# TPaletteWindow.net
KiCad netlist of a schematic drawn in Altium Designer
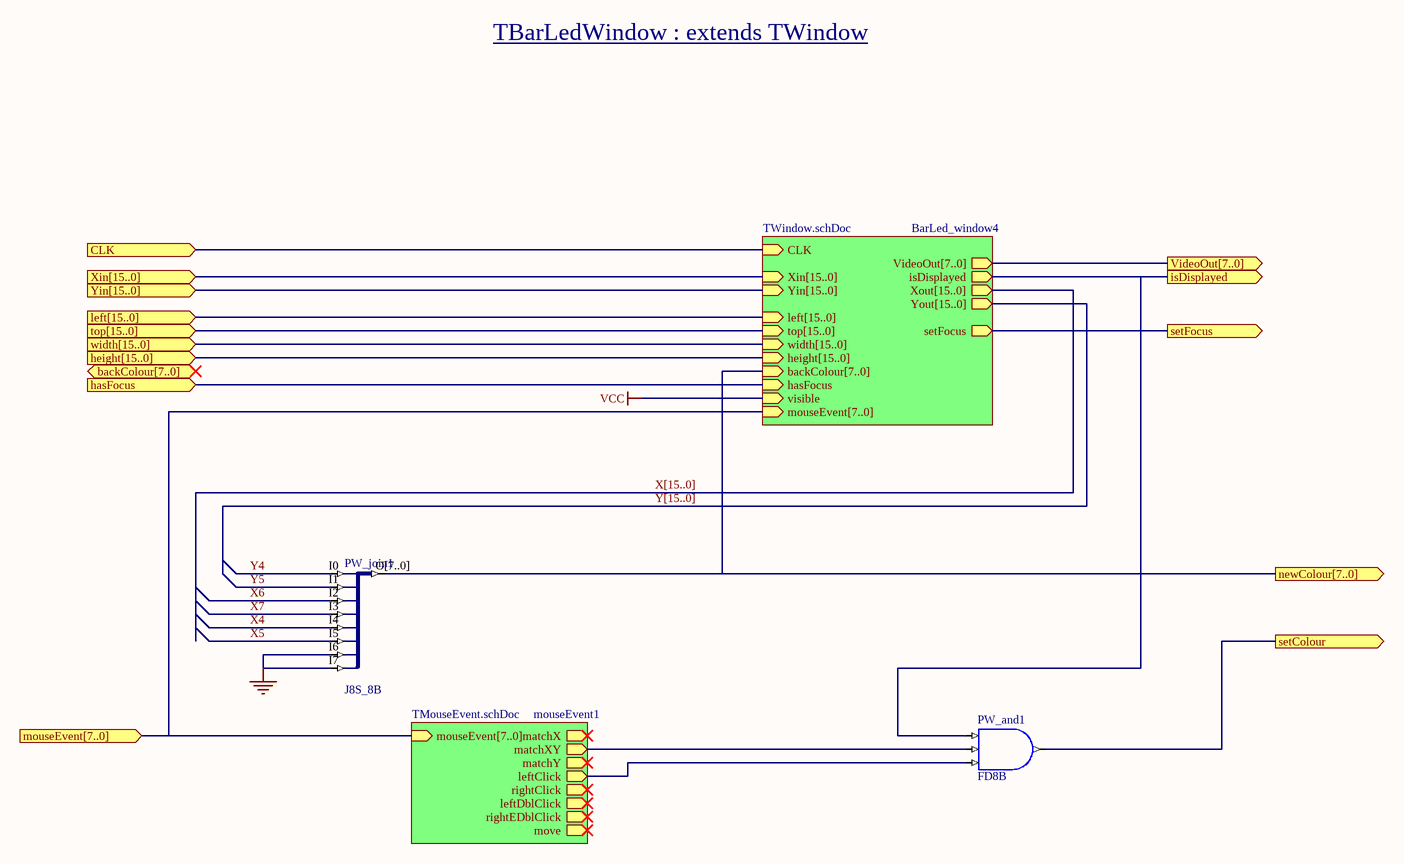
[diagram p0: TPaletteWindow.schDOC]

(export (version "E")
  (design (tool "Eeschema 10.0.6"))
  (components
    (comp (ref "PW_and1")
      (value "FD8B")
      (description "3-Input AND Gate, Single Pin Version")
      (fields (field (name "PUBLISHER") "Altium Limited"))
      (libsource (lib "FPGA Generic") (part "AND3S"))
    )
    (comp (ref "PW_join1")
      (value "J8S_8B")
      (description "8 Single pin inputs to single 8-Bit output bus")
      (fields (field (name "PUBLISHER") "Altium Limited"))
      (libsource (lib "FPGA Generic") (part "J8S_8B"))
    )
  )
  (nets
    (net (code "157") (name "/X4") (class "Default")
      (node (ref "PW_join1") (pin "I4") (pinfunction "I4_I4") (pintype "input"))
    )
    (net (code "158") (name "/X5") (class "Default")
      (node (ref "PW_join1") (pin "I5") (pinfunction "I5_I5") (pintype "input"))
    )
    (net (code "159") (name "/X6") (class "Default")
      (node (ref "PW_join1") (pin "I2") (pinfunction "I2_I2") (pintype "input"))
    )
    (net (code "160") (name "/X7") (class "Default")
      (node (ref "PW_join1") (pin "I3") (pinfunction "I3_I3") (pintype "input"))
    )
    (net (code "163") (name "/Y4") (class "Default")
      (node (ref "PW_join1") (pin "I0") (pinfunction "I0_I0") (pintype "input"))
    )
    (net (code "164") (name "/Y5") (class "Default")
      (node (ref "PW_join1") (pin "I1") (pinfunction "I1_I1") (pintype "input"))
    )
    (net (code "170") (name "/isDisplayed") (class "Default")
      (node (ref "PW_and1") (pin "I0") (pinfunction "I0_I0") (pintype "input"))
    )
    (net (code "171") (name "/leftClick") (class "Default")
      (node (ref "PW_and1") (pin "I2") (pinfunction "I2_I2") (pintype "input"))
    )
    (net (code "175") (name "/matchXY") (class "Default")
      (node (ref "PW_and1") (pin "I1") (pinfunction "I1_I1") (pintype "input"))
    )
    (net (code "180") (name "/newColour[7..0]") (class "Default")
      (node (ref "PW_join1") (pin "O[7..0]") (pinfunction "O[7..0]_O[7..0]") (pintype "output"))
    )
    (net (code "183") (name "/setColour") (class "Default")
      (node (ref "PW_and1") (pin "O") (pinfunction "O_O") (pintype "output"))
    )
    (net (code "187") (name "GND") (class "Default")
      (node (ref "PW_join1") (pin "I6") (pinfunction "I6_I6") (pintype "input"))
      (node (ref "PW_join1") (pin "I7") (pinfunction "I7_I7") (pintype "input"))
    )
  )
)
